# ProDoc_TwinWave_2026-01-11.net
KiCad netlist of a schematic drawn in EasyEDA Pro
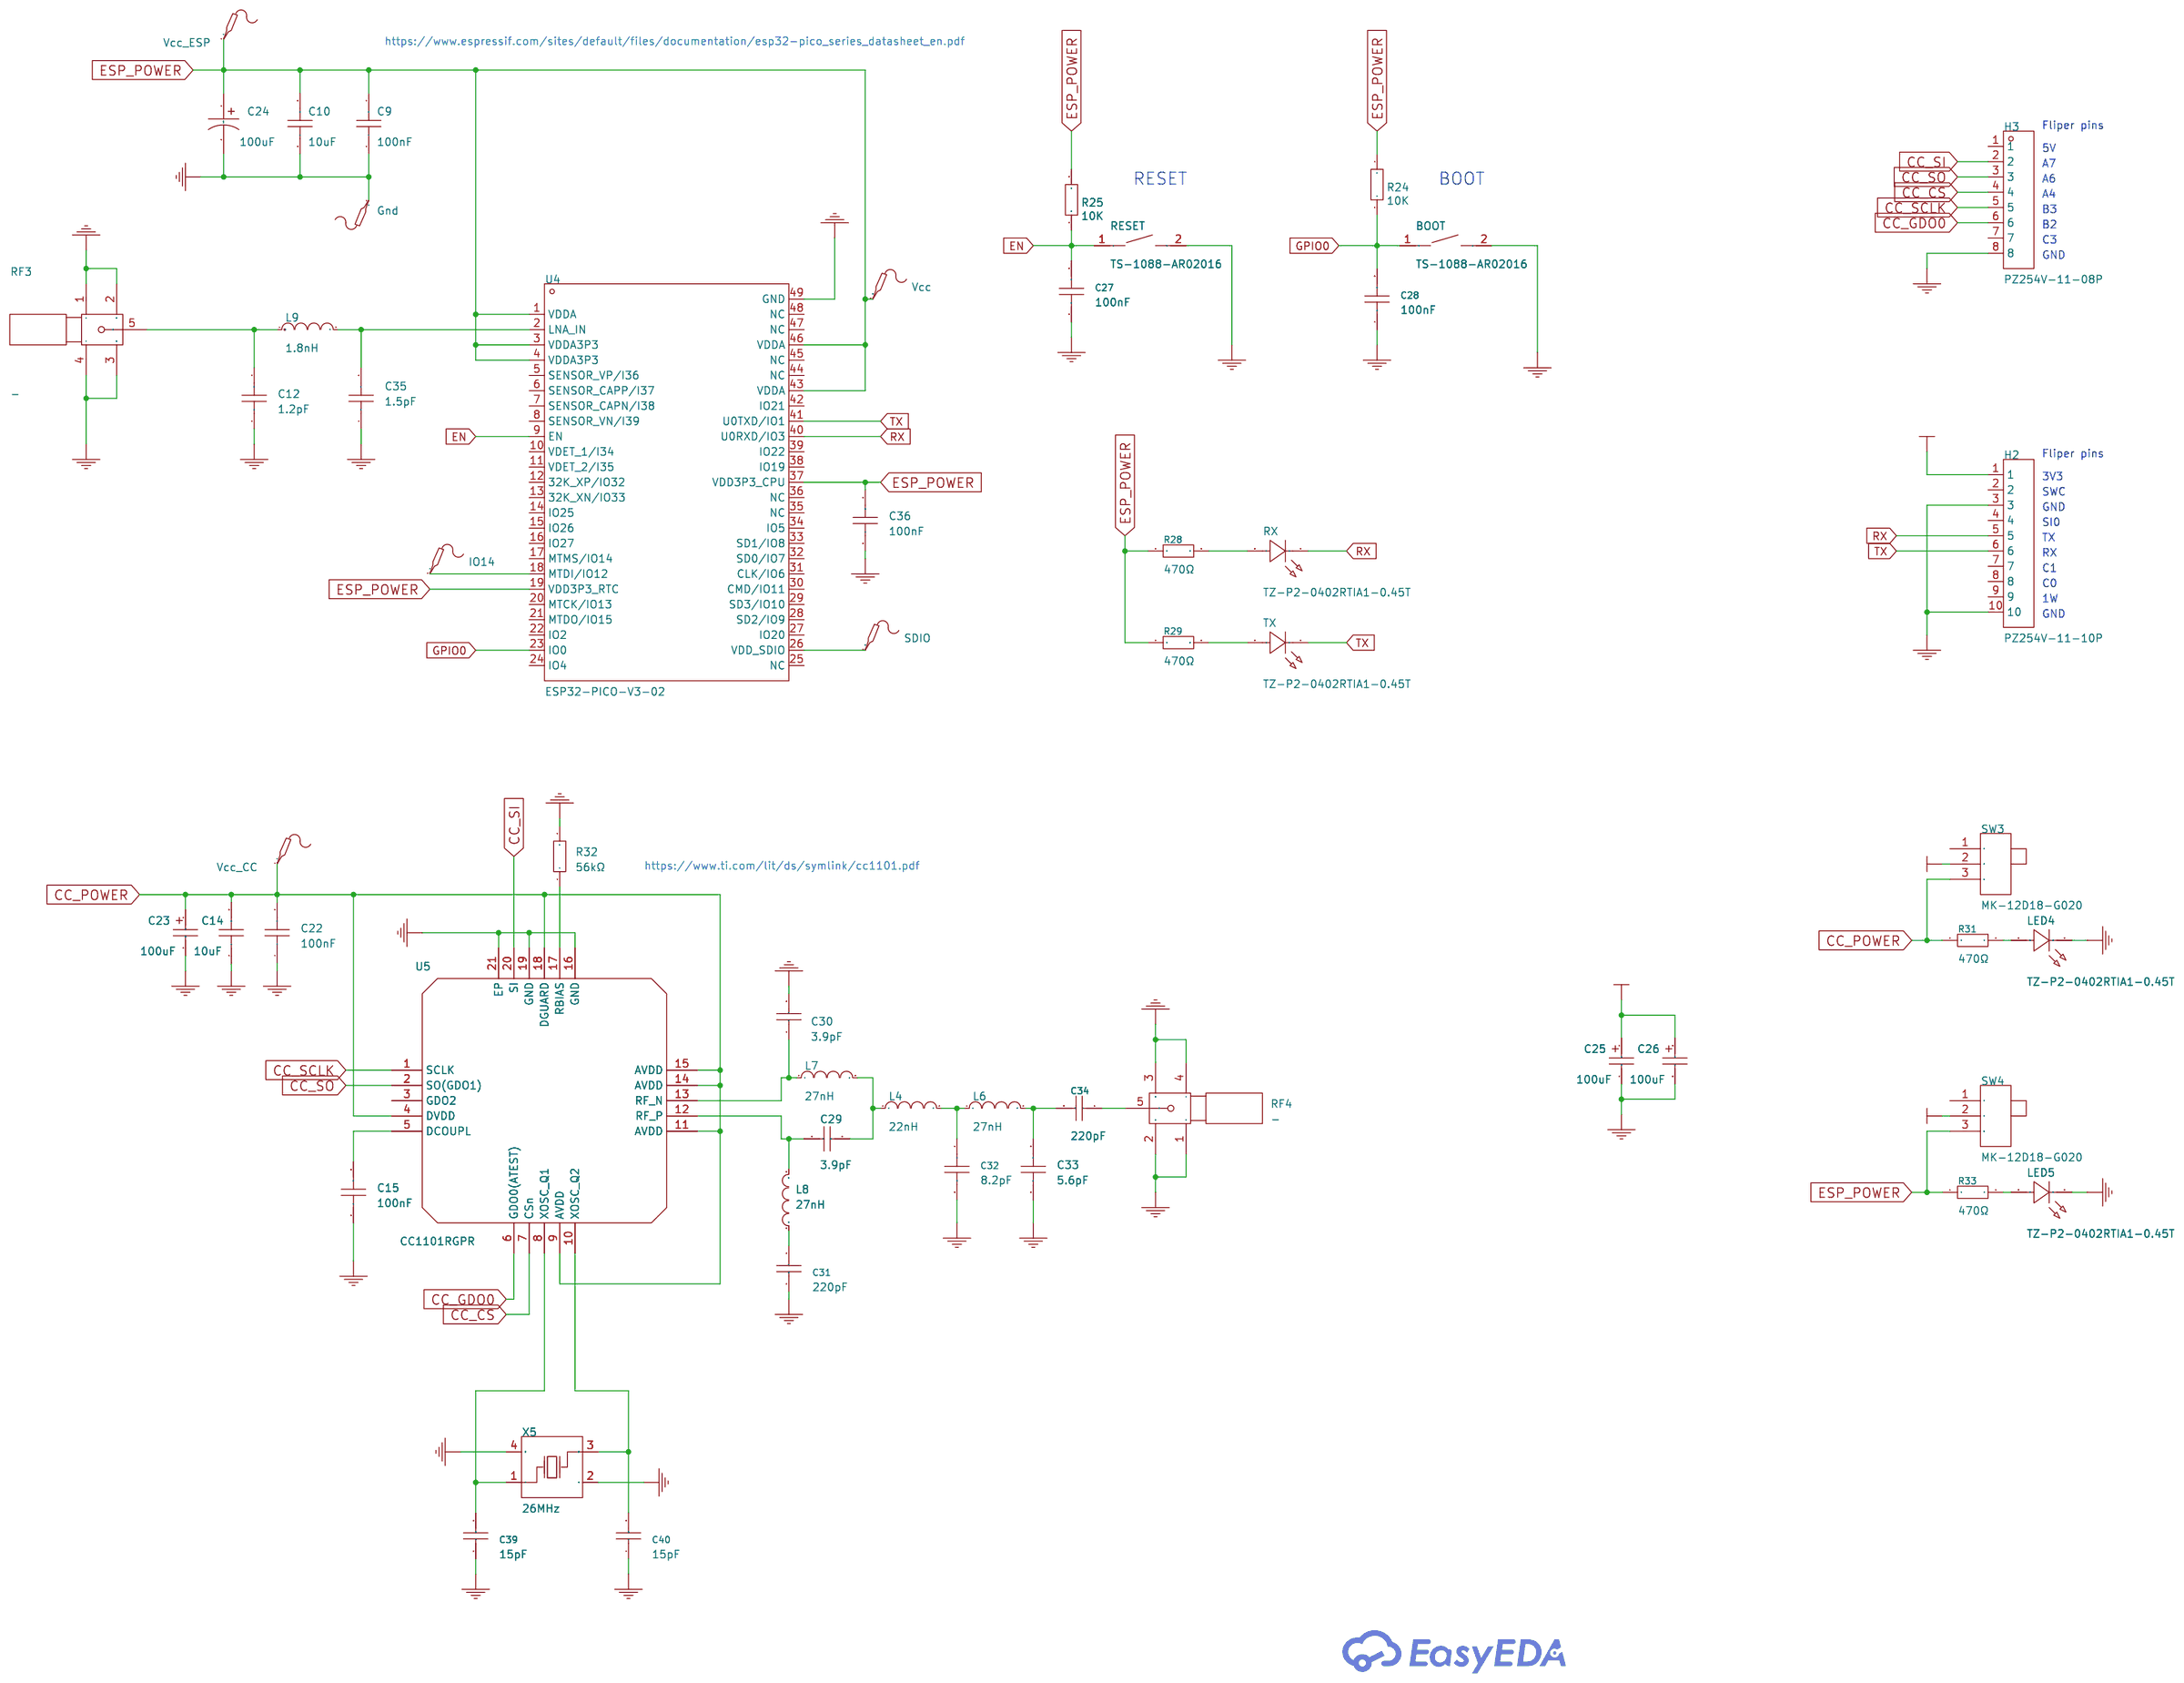
[diagram p0: schematic sheet]

(export (version "E")
  (design (tool "Eeschema 10.0.6"))
  (components
    (comp (ref "BOOT")
      (value "TS-1088-AR02016")
      (footprint "easyedapro:SW-SMD_L3.9-W3.0-P4.45")
      (fields (field (name "Manufacturer") "XUNPU(讯普)"))
      (libsource (lib "easyedapro") (part "TS-1088-AR02016"))
    )
    (comp (ref "C9")
      (value "100nF")
      (footprint "easyedapro:C0603")
      (description "Capacitance:100nF Tolerance:±10% Tolerance:±10% Voltage Rating:50V Temperature Coefficient:X7R")
      (fields
        (field (name "Manufacturer Part") "CC0603KRX7R9BB104")
        (field (name "Manufacturer") "YAGEO(国巨)")
      )
      (libsource (lib "easyedapro") (part "CC0603KRX7R9BB104"))
    )
    (comp (ref "C10")
      (value "10uF")
      (footprint "easyedapro:C0603")
      (fields
        (field (name "Manufacturer Part") "CL10A106MP8NNNC")
        (field (name "Manufacturer") "SAMSUNG(三星)")
      )
      (libsource (lib "easyedapro") (part "CL10A106MP8NNNC"))
    )
    (comp (ref "C12")
      (value "1.2pF")
      (footprint "easyedapro:C0201")
      (fields
        (field (name "Manufacturer Part") "GRM0335C1H1R2BA01D")
        (field (name "Manufacturer") "muRata(村田)")
      )
      (libsource (lib "easyedapro") (part "GRM0335C1H1R2BA01D"))
    )
    (comp (ref "C14")
      (value "10uF")
      (footprint "easyedapro:C0603")
      (fields
        (field (name "Manufacturer Part") "CL10A106MP8NNNC")
        (field (name "Manufacturer") "SAMSUNG(三星)")
      )
      (libsource (lib "easyedapro") (part "CL10A106MP8NNNC"))
    )
    (comp (ref "C15")
      (value "100nF")
      (footprint "easyedapro:C0603")
      (description "Capacitance:100nF Tolerance:±10% Tolerance:±10% Voltage Rating:50V Temperature Coefficient:X7R")
      (fields
        (field (name "Manufacturer Part") "CC0603KRX7R9BB104")
        (field (name "Manufacturer") "YAGEO(国巨)")
      )
      (libsource (lib "easyedapro") (part "CC0603KRX7R9BB104"))
    )
    (comp (ref "C22")
      (value "100nF")
      (footprint "easyedapro:C0603")
      (description "Capacitance:100nF Tolerance:±10% Tolerance:±10% Voltage Rating:50V Temperature Coefficient:X7R")
      (fields
        (field (name "Manufacturer Part") "CC0603KRX7R9BB104")
        (field (name "Manufacturer") "YAGEO(国巨)")
      )
      (libsource (lib "easyedapro") (part "CC0603KRX7R9BB104"))
    )
    (comp (ref "C23")
      (value "100uF")
      (footprint "easyedapro:CASE-B_3528")
      (fields (field (name "Manufacturer Part") "TAJB107K006RNJ") (field (name "Manufacturer") "Kyocera AVX"))
      (libsource (lib "easyedapro") (part "TAJB107K006RNJ"))
    )
    (comp (ref "C24")
      (value "100uF")
      (footprint "easyedapro:CASE-B_3528-1")
      (fields
        (field (name "Manufacturer Part") "TPSB107K006R0250")
        (field (name "Manufacturer") "Kyocera AVX")
      )
      (libsource (lib "easyedapro") (part "TPSB107K006R0250"))
    )
    (comp (ref "C25")
      (value "100uF")
      (footprint "easyedapro:CASE-B_3528")
      (fields (field (name "Manufacturer Part") "TAJB107K006RNJ") (field (name "Manufacturer") "Kyocera AVX"))
      (libsource (lib "easyedapro") (part "TAJB107K006RNJ"))
    )
    (comp (ref "C26")
      (value "100uF")
      (footprint "easyedapro:CASE-B_3528")
      (fields (field (name "Manufacturer Part") "TAJB107K006RNJ") (field (name "Manufacturer") "Kyocera AVX"))
      (libsource (lib "easyedapro") (part "TAJB107K006RNJ"))
    )
    (comp (ref "C27")
      (value "100nF")
      (footprint "easyedapro:C0402")
      (fields
        (field (name "Manufacturer Part") "CC0402KRX7R7BB104")
        (field (name "Manufacturer") "YAGEO(国巨)")
      )
      (libsource (lib "easyedapro") (part "CC0402KRX7R7BB104"))
    )
    (comp (ref "C28")
      (value "100nF")
      (footprint "easyedapro:C0402")
      (fields
        (field (name "Manufacturer Part") "CC0402KRX7R7BB104")
        (field (name "Manufacturer") "YAGEO(国巨)")
      )
      (libsource (lib "easyedapro") (part "CC0402KRX7R7BB104"))
    )
    (comp (ref "C29")
      (value "3.9pF")
      (footprint "easyedapro:C0402")
      (fields (field (name "Manufacturer Part") "0402CG3R9C500NT") (field (name "Manufacturer") "FH(风华)"))
      (libsource (lib "easyedapro") (part "0402CG3R9C500NT"))
    )
    (comp (ref "C30")
      (value "3.9pF")
      (footprint "easyedapro:C0402")
      (fields (field (name "Manufacturer Part") "0402CG3R9C500NT") (field (name "Manufacturer") "FH(风华)"))
      (libsource (lib "easyedapro") (part "0402CG3R9C500NT"))
    )
    (comp (ref "C31")
      (value "220pF")
      (footprint "easyedapro:C0402")
      (description "Capacitance:220pF Tolerance:±5% Tolerance:±5% Voltage Rating:50V Temperature Coefficient:NP0")
      (fields
        (field (name "Manufacturer Part") "CC0402JRNPO9BN221")
        (field (name "Manufacturer") "YAGEO(国巨)")
      )
      (libsource (lib "easyedapro") (part "CC0402JRNPO9BN221"))
    )
    (comp (ref "C32")
      (value "8.2pF")
      (footprint "easyedapro:C0402")
      (fields
        (field (name "Manufacturer Part") "CC0402BRNPO9BN8R2")
        (field (name "Manufacturer") "YAGEO(国巨)")
      )
      (libsource (lib "easyedapro") (part "CC0402BRNPO9BN8R2"))
    )
    (comp (ref "C33")
      (value "5.6pF")
      (footprint "easyedapro:C0402")
      (fields
        (field (name "Manufacturer Part") "CC0402BRNPO9BN5R6")
        (field (name "Manufacturer") "YAGEO(国巨)")
      )
      (libsource (lib "easyedapro") (part "CC0402BRNPO9BN5R6"))
    )
    (comp (ref "C34")
      (value "220pF")
      (footprint "easyedapro:C0402")
      (description "Capacitance:220pF Tolerance:±5% Tolerance:±5% Voltage Rating:50V Temperature Coefficient:NP0")
      (fields
        (field (name "Manufacturer Part") "CC0402JRNPO9BN221")
        (field (name "Manufacturer") "YAGEO(国巨)")
      )
      (libsource (lib "easyedapro") (part "CC0402JRNPO9BN221"))
    )
    (comp (ref "C35")
      (value "1.5pF")
      (footprint "easyedapro:C0201")
      (fields
        (field (name "Manufacturer Part") "GRM0335C1H1R5BA01D")
        (field (name "Manufacturer") "muRata(村田)")
      )
      (libsource (lib "easyedapro") (part "GRM0335C1H1R5BA01D"))
    )
    (comp (ref "C36")
      (value "100nF")
      (footprint "easyedapro:C0603")
      (description "Capacitance:100nF Tolerance:±10% Tolerance:±10% Voltage Rating:50V Temperature Coefficient:X7R")
      (fields
        (field (name "Manufacturer Part") "CC0603KRX7R9BB104")
        (field (name "Manufacturer") "YAGEO(国巨)")
      )
      (libsource (lib "easyedapro") (part "CC0603KRX7R9BB104"))
    )
    (comp (ref "C39")
      (value "15pF")
      (footprint "easyedapro:C0402")
      (fields
        (field (name "Manufacturer Part") "CC0402JRNPO9BN150")
        (field (name "Manufacturer") "YAGEO(国巨)")
      )
      (libsource (lib "easyedapro") (part "CC0402JRNPO9BN150"))
    )
    (comp (ref "C40")
      (value "15pF")
      (footprint "easyedapro:C0402")
      (fields
        (field (name "Manufacturer Part") "CC0402JRNPO9BN150")
        (field (name "Manufacturer") "YAGEO(国巨)")
      )
      (libsource (lib "easyedapro") (part "CC0402JRNPO9BN150"))
    )
    (comp (ref "Gnd")
      (value "~")
      (footprint "easyedapro:Test-Point-0.5mm")
      (description "Test Point 测试点")
      (libsource (lib "easyedapro") (part "Test-Point"))
    )
    (comp (ref "H2")
      (value "PZ254V-11-10P")
      (footprint "easyedapro:HDR-TH_10P-P2.54-V-M")
      (fields (field (name "Manufacturer") "XFCN(兴飞)"))
      (libsource (lib "easyedapro") (part "PZ254V-11-10P"))
    )
    (comp (ref "H3")
      (value "PZ254V-11-08P")
      (footprint "easyedapro:HDR-TH_8P-P2.54-V-M")
      (fields (field (name "Manufacturer") "XFCN(兴飞)"))
      (libsource (lib "easyedapro") (part "PZ254V-11-08P"))
    )
    (comp (ref "IO14")
      (value "~")
      (footprint "easyedapro:Test-Point-0.5mm")
      (description "Test Point 测试点")
      (libsource (lib "easyedapro") (part "Test-Point"))
    )
    (comp (ref "L4")
      (value "22nH")
      (footprint "easyedapro:L0402")
      (fields (field (name "Manufacturer Part") "LQG15HS22NJ02D") (field (name "Manufacturer") "muRata(村田)"))
      (libsource (lib "easyedapro") (part "LQG15HS22NJ02D"))
    )
    (comp (ref "L6")
      (value "27nH")
      (footprint "easyedapro:L0402-RD")
      (fields (field (name "Manufacturer Part") "LQG15HS27NJ02D") (field (name "Manufacturer") "muRata(村田)"))
      (libsource (lib "easyedapro") (part "LQG15HS27NJ02D"))
    )
    (comp (ref "L7")
      (value "27nH")
      (footprint "easyedapro:L0402-RD")
      (fields (field (name "Manufacturer Part") "LQG15HS27NJ02D") (field (name "Manufacturer") "muRata(村田)"))
      (libsource (lib "easyedapro") (part "LQG15HS27NJ02D"))
    )
    (comp (ref "L8")
      (value "27nH")
      (footprint "easyedapro:L0402-RD")
      (fields (field (name "Manufacturer Part") "LQG15HS27NJ02D") (field (name "Manufacturer") "muRata(村田)"))
      (libsource (lib "easyedapro") (part "LQG15HS27NJ02D"))
    )
    (comp (ref "L9")
      (value "1.8nH")
      (footprint "easyedapro:L0201-RD")
      (fields (field (name "Manufacturer Part") "LQP03TN1N8B02D") (field (name "Manufacturer") "muRata(村田)"))
      (libsource (lib "easyedapro") (part "LQP03TN1N8B02D"))
    )
    (comp (ref "LED4")
      (value "TZ-P2-0402RTIA1-0.45T")
      (footprint "easyedapro:LED0402-RD_RED")
      (fields (field (name "Manufacturer") "TUOZHAN(拓展光电)"))
      (libsource (lib "easyedapro") (part "TZ-P2-0402RTIA1-0.45T"))
    )
    (comp (ref "LED5")
      (value "TZ-P2-0402RTIA1-0.45T")
      (footprint "easyedapro:LED0402-RD_RED")
      (fields (field (name "Manufacturer") "TUOZHAN(拓展光电)"))
      (libsource (lib "easyedapro") (part "TZ-P2-0402RTIA1-0.45T"))
    )
    (comp (ref "R24")
      (value "10K")
      (footprint "easyedapro:R0603")
      (fields (field (name "Manufacturer Part") "RC0603DR-0710KL") (field (name "Manufacturer") "YAGEO(国巨)"))
      (libsource (lib "easyedapro") (part "10K"))
    )
    (comp (ref "R25")
      (value "10K")
      (footprint "easyedapro:R0603")
      (fields (field (name "Manufacturer Part") "RC0603DR-0710KL") (field (name "Manufacturer") "YAGEO(国巨)"))
      (libsource (lib "easyedapro") (part "10K"))
    )
    (comp (ref "R28")
      (value "470Ω")
      (footprint "easyedapro:R0402")
      (fields
        (field (name "Manufacturer Part") "0402WGF4700TCE")
        (field (name "Manufacturer") "UNI-ROYAL(厚声)")
      )
      (libsource (lib "easyedapro") (part "0402WGF4700TCE"))
    )
    (comp (ref "R29")
      (value "470Ω")
      (footprint "easyedapro:R0402")
      (fields
        (field (name "Manufacturer Part") "0402WGF4700TCE")
        (field (name "Manufacturer") "UNI-ROYAL(厚声)")
      )
      (libsource (lib "easyedapro") (part "0402WGF4700TCE"))
    )
    (comp (ref "R31")
      (value "470Ω")
      (footprint "easyedapro:R0402")
      (fields
        (field (name "Manufacturer Part") "0402WGF4700TCE")
        (field (name "Manufacturer") "UNI-ROYAL(厚声)")
      )
      (libsource (lib "easyedapro") (part "0402WGF4700TCE"))
    )
    (comp (ref "R32")
      (value "56kΩ")
      (footprint "easyedapro:R0402")
      (fields
        (field (name "Manufacturer Part") "0402WGF5602TCE")
        (field (name "Manufacturer") "UNI-ROYAL(厚声)")
      )
      (libsource (lib "easyedapro") (part "0402WGF5602TCE"))
    )
    (comp (ref "R33")
      (value "470Ω")
      (footprint "easyedapro:R0402")
      (fields
        (field (name "Manufacturer Part") "0402WGF4700TCE")
        (field (name "Manufacturer") "UNI-ROYAL(厚声)")
      )
      (libsource (lib "easyedapro") (part "0402WGF4700TCE"))
    )
    (comp (ref "RESET")
      (value "TS-1088-AR02016")
      (footprint "easyedapro:SW-SMD_L3.9-W3.0-P4.45")
      (fields (field (name "Manufacturer") "XUNPU(讯普)"))
      (libsource (lib "easyedapro") (part "TS-1088-AR02016"))
    )
    (comp (ref "RF3")
      (value "-")
      (footprint "easyedapro:SMA-SMD_BWSMA-KE-P001")
      (fields
        (field (name "Manufacturer Part") "BWSMA-KE-P001")
        (field (name "Manufacturer") "BAT WIRELESS(蝙蝠无线)")
      )
      (libsource (lib "easyedapro") (part "BWSMA-KE-P001"))
    )
    (comp (ref "RF4")
      (value "-")
      (footprint "easyedapro:SMA-SMD_BWSMA-KE-P001")
      (fields
        (field (name "Manufacturer Part") "BWSMA-KE-P001")
        (field (name "Manufacturer") "BAT WIRELESS(蝙蝠无线)")
      )
      (libsource (lib "easyedapro") (part "BWSMA-KE-P001"))
    )
    (comp (ref "RX")
      (value "TZ-P2-0402RTIA1-0.45T")
      (footprint "easyedapro:LED0402-RD_RED")
      (fields (field (name "Manufacturer") "TUOZHAN(拓展光电)"))
      (libsource (lib "easyedapro") (part "TZ-P2-0402RTIA1-0.45T"))
    )
    (comp (ref "SDIO")
      (value "~")
      (footprint "easyedapro:Test-Point-0.5mm")
      (description "Test Point 测试点")
      (libsource (lib "easyedapro") (part "Test-Point"))
    )
    (comp (ref "SW3")
      (value "MK-12D18-G020")
      (footprint "easyedapro:SW-TH_MK-12D18-G040")
      (fields (field (name "Manufacturer") "G-Switch(品赞)"))
      (libsource (lib "easyedapro") (part "MK-12D18-G020"))
    )
    (comp (ref "SW4")
      (value "MK-12D18-G020")
      (footprint "easyedapro:SW-TH_MK-12D18-G040")
      (fields (field (name "Manufacturer") "G-Switch(品赞)"))
      (libsource (lib "easyedapro") (part "MK-12D18-G020"))
    )
    (comp (ref "TX")
      (value "TZ-P2-0402RTIA1-0.45T")
      (footprint "easyedapro:LED0402-RD_RED")
      (fields (field (name "Manufacturer") "TUOZHAN(拓展光电)"))
      (libsource (lib "easyedapro") (part "TZ-P2-0402RTIA1-0.45T"))
    )
    (comp (ref "U4")
      (value "ESP32-PICO-V3-02")
      (footprint "easyedapro:QFN-48_L7.0-W7.0-P0.50-BL-EP5.1")
      (fields (field (name "Manufacturer") "ESPRESSIF(乐鑫)"))
      (libsource (lib "easyedapro") (part "ESP32-PICO-V3-02"))
    )
    (comp (ref "U5")
      (value "CC1101RGPR")
      (footprint "easyedapro:QFN-20_L4.0-W4.0-P0.5-TL-EP")
      (fields (field (name "Manufacturer") "TI(德州仪器)"))
      (libsource (lib "easyedapro") (part "CC1101RGPR"))
    )
    (comp (ref "Vcc")
      (value "~")
      (footprint "easyedapro:Test-Point-0.5mm")
      (description "Test Point 测试点")
      (libsource (lib "easyedapro") (part "Test-Point"))
    )
    (comp (ref "Vcc_CC")
      (value "~")
      (footprint "easyedapro:Test-Point-0.5mm")
      (description "Test Point 测试点")
      (libsource (lib "easyedapro") (part "Test-Point"))
    )
    (comp (ref "Vcc_ESP")
      (value "~")
      (footprint "easyedapro:Test-Point-0.5mm")
      (description "Test Point 测试点")
      (libsource (lib "easyedapro") (part "Test-Point"))
    )
    (comp (ref "X5")
      (value "26MHz")
      (footprint "easyedapro:CRYSTAL-SMD_4P-L3.2-W2.5-BL")
      (fields (field (name "Manufacturer Part") "X322526MMB4SI") (field (name "Manufacturer") "YXC(扬兴晶振)"))
      (libsource (lib "easyedapro") (part "X322526MMB4SI"))
    )
  )
  (nets
    (net (code "1") (name "3V3") (class "Default")
      (node (ref "C25") (pin "1") (pinfunction "1_1") (pintype "input"))
      (node (ref "C26") (pin "1") (pinfunction "1_1") (pintype "input"))
      (node (ref "H2") (pin "1") (pinfunction "1_1") (pintype "unspecified"))
      (node (ref "SW3") (pin "2") (pinfunction "2_2") (pintype "unspecified"))
      (node (ref "SW4") (pin "2") (pinfunction "2_2") (pintype "unspecified"))
    )
    (net (code "2") (name "CC_CS") (class "Default")
      (node (ref "H3") (pin "4") (pinfunction "4_4") (pintype "unspecified"))
      (node (ref "U5") (pin "7") (pinfunction "CSn_7") (pintype "unspecified"))
    )
    (net (code "3") (name "CC_GDO0") (class "Default")
      (node (ref "H3") (pin "6") (pinfunction "6_6") (pintype "unspecified"))
      (node (ref "U5") (pin "6") (pinfunction "GDO0(ATEST)_6") (pintype "unspecified"))
    )
    (net (code "4") (name "CC_POWER") (class "Default")
      (node (ref "C14") (pin "2") (pinfunction "2_2") (pintype "unspecified"))
      (node (ref "C22") (pin "2") (pinfunction "2_2") (pintype "unspecified"))
      (node (ref "C23") (pin "1") (pinfunction "1_1") (pintype "input"))
      (node (ref "R31") (pin "1") (pinfunction "1_1") (pintype "input"))
      (node (ref "SW3") (pin "3") (pinfunction "3_3") (pintype "unspecified"))
      (node (ref "U5") (pin "11") (pinfunction "AVDD_11") (pintype "unspecified"))
      (node (ref "U5") (pin "14") (pinfunction "AVDD_14") (pintype "unspecified"))
      (node (ref "U5") (pin "15") (pinfunction "AVDD_15") (pintype "unspecified"))
      (node (ref "U5") (pin "18") (pinfunction "DGUARD_18") (pintype "unspecified"))
      (node (ref "U5") (pin "4") (pinfunction "DVDD_4") (pintype "unspecified"))
      (node (ref "U5") (pin "9") (pinfunction "AVDD_9") (pintype "unspecified"))
      (node (ref "Vcc_CC") (pin "1") (pinfunction "1_1") (pintype "unspecified"))
    )
    (net (code "5") (name "CC_SCLK") (class "Default")
      (node (ref "H3") (pin "5") (pinfunction "5_5") (pintype "unspecified"))
      (node (ref "U5") (pin "1") (pinfunction "SCLK_1") (pintype "unspecified"))
    )
    (net (code "6") (name "CC_SI") (class "Default")
      (node (ref "H3") (pin "2") (pinfunction "2_2") (pintype "unspecified"))
      (node (ref "U5") (pin "20") (pinfunction "SI_20") (pintype "unspecified"))
    )
    (net (code "7") (name "CC_SO") (class "Default")
      (node (ref "H3") (pin "3") (pinfunction "3_3") (pintype "unspecified"))
      (node (ref "U5") (pin "2") (pinfunction "SO(GDO1)_2") (pintype "unspecified"))
    )
    (net (code "8") (name "EN") (class "Default")
      (node (ref "C27") (pin "2") (pinfunction "2_2") (pintype "input"))
      (node (ref "R25") (pin "1") (pinfunction "1_1") (pintype "input"))
      (node (ref "RESET") (pin "1") (pinfunction "1_1") (pintype "unspecified"))
      (node (ref "U4") (pin "9") (pinfunction "EN_9") (pintype "unspecified"))
    )
    (net (code "9") (name "ESP_POWER") (class "Default")
      (node (ref "C10") (pin "2") (pinfunction "2_2") (pintype "unspecified"))
      (node (ref "C24") (pin "1") (pinfunction "1_1") (pintype "unspecified"))
      (node (ref "C36") (pin "2") (pinfunction "2_2") (pintype "unspecified"))
      (node (ref "C9") (pin "2") (pinfunction "2_2") (pintype "unspecified"))
      (node (ref "R24") (pin "2") (pinfunction "2_2") (pintype "input"))
      (node (ref "R25") (pin "2") (pinfunction "2_2") (pintype "input"))
      (node (ref "R28") (pin "1") (pinfunction "1_1") (pintype "input"))
      (node (ref "R29") (pin "1") (pinfunction "1_1") (pintype "input"))
      (node (ref "R33") (pin "1") (pinfunction "1_1") (pintype "input"))
      (node (ref "SW4") (pin "3") (pinfunction "3_3") (pintype "unspecified"))
      (node (ref "U4") (pin "1") (pinfunction "VDDA_1") (pintype "unspecified"))
      (node (ref "U4") (pin "19") (pinfunction "VDD3P3_RTC_19") (pintype "unspecified"))
      (node (ref "U4") (pin "3") (pinfunction "VDDA3P3_3") (pintype "unspecified"))
      (node (ref "U4") (pin "37") (pinfunction "VDD3P3_CPU_37") (pintype "unspecified"))
      (node (ref "U4") (pin "4") (pinfunction "VDDA3P3_4") (pintype "unspecified"))
      (node (ref "U4") (pin "43") (pinfunction "VDDA_43") (pintype "unspecified"))
      (node (ref "U4") (pin "46") (pinfunction "VDDA_46") (pintype "unspecified"))
      (node (ref "Vcc") (pin "1") (pinfunction "1_1") (pintype "unspecified"))
      (node (ref "Vcc_ESP") (pin "1") (pinfunction "1_1") (pintype "unspecified"))
    )
    (net (code "10") (name "GND") (class "Default")
      (node (ref "BOOT") (pin "2") (pinfunction "2_2") (pintype "unspecified"))
      (node (ref "C10") (pin "1") (pinfunction "1_1") (pintype "unspecified"))
      (node (ref "C12") (pin "1") (pinfunction "1_1") (pintype "unspecified"))
      (node (ref "C14") (pin "1") (pinfunction "1_1") (pintype "unspecified"))
      (node (ref "C15") (pin "1") (pinfunction "1_1") (pintype "unspecified"))
      (node (ref "C22") (pin "1") (pinfunction "1_1") (pintype "unspecified"))
      (node (ref "C23") (pin "2") (pinfunction "2_2") (pintype "input"))
      (node (ref "C24") (pin "2") (pinfunction "2_2") (pintype "unspecified"))
      (node (ref "C25") (pin "2") (pinfunction "2_2") (pintype "input"))
      (node (ref "C26") (pin "2") (pinfunction "2_2") (pintype "input"))
      (node (ref "C27") (pin "1") (pinfunction "1_1") (pintype "input"))
      (node (ref "C28") (pin "1") (pinfunction "1_1") (pintype "input"))
      (node (ref "C30") (pin "2") (pinfunction "2_2") (pintype "input"))
      (node (ref "C31") (pin "1") (pinfunction "1_1") (pintype "input"))
      (node (ref "C32") (pin "2") (pinfunction "2_2") (pintype "input"))
      (node (ref "C33") (pin "1") (pinfunction "1_1") (pintype "unspecified"))
      (node (ref "C35") (pin "1") (pinfunction "1_1") (pintype "unspecified"))
      (node (ref "C36") (pin "1") (pinfunction "1_1") (pintype "unspecified"))
      (node (ref "C39") (pin "1") (pinfunction "1_1") (pintype "input"))
      (node (ref "C40") (pin "1") (pinfunction "1_1") (pintype "input"))
      (node (ref "C9") (pin "1") (pinfunction "1_1") (pintype "unspecified"))
      (node (ref "Gnd") (pin "1") (pinfunction "1_1") (pintype "unspecified"))
      (node (ref "H2") (pin "10") (pinfunction "10_10") (pintype "unspecified"))
      (node (ref "H2") (pin "3") (pinfunction "3_3") (pintype "unspecified"))
      (node (ref "H3") (pin "8") (pinfunction "8_8") (pintype "unspecified"))
      (node (ref "LED4") (pin "1") (pinfunction "K_1") (pintype "unspecified"))
      (node (ref "LED5") (pin "1") (pinfunction "K_1") (pintype "unspecified"))
      (node (ref "R32") (pin "2") (pinfunction "2_2") (pintype "input"))
      (node (ref "RESET") (pin "2") (pinfunction "2_2") (pintype "unspecified"))
      (node (ref "RF3") (pin "1") (pinfunction "1_1") (pintype "unspecified"))
      (node (ref "RF3") (pin "2") (pinfunction "2_2") (pintype "unspecified"))
      (node (ref "RF3") (pin "3") (pinfunction "3_3") (pintype "unspecified"))
      (node (ref "RF3") (pin "4") (pinfunction "4_4") (pintype "unspecified"))
      (node (ref "RF4") (pin "1") (pinfunction "1_1") (pintype "unspecified"))
      (node (ref "RF4") (pin "2") (pinfunction "2_2") (pintype "unspecified"))
      (node (ref "RF4") (pin "3") (pinfunction "3_3") (pintype "unspecified"))
      (node (ref "RF4") (pin "4") (pinfunction "4_4") (pintype "unspecified"))
      (node (ref "U4") (pin "49") (pinfunction "GND_49") (pintype "unspecified"))
      (node (ref "U5") (pin "16") (pinfunction "GND_16") (pintype "unspecified"))
      (node (ref "U5") (pin "19") (pinfunction "GND_19") (pintype "unspecified"))
      (node (ref "U5") (pin "21") (pinfunction "EP_21") (pintype "unspecified"))
      (node (ref "X5") (pin "2") (pinfunction "GND_2") (pintype "unspecified"))
      (node (ref "X5") (pin "4") (pinfunction "GND_4") (pintype "unspecified"))
    )
    (net (code "11") (name "GPIO0") (class "Default")
      (node (ref "BOOT") (pin "1") (pinfunction "1_1") (pintype "unspecified"))
      (node (ref "C28") (pin "2") (pinfunction "2_2") (pintype "input"))
      (node (ref "R24") (pin "1") (pinfunction "1_1") (pintype "input"))
      (node (ref "U4") (pin "23") (pinfunction "IO0_23") (pintype "unspecified"))
    )
    (net (code "12") (name "Net-(C12-Pad2)") (class "Default")
      (node (ref "C12") (pin "2") (pinfunction "2_2") (pintype "unspecified"))
      (node (ref "L9") (pin "1") (pinfunction "1_1") (pintype "input"))
      (node (ref "RF3") (pin "5") (pinfunction "5_5") (pintype "unspecified"))
    )
    (net (code "13") (name "Net-(C29-Pad2)") (class "Default")
      (node (ref "C29") (pin "2") (pinfunction "2_2") (pintype "input"))
      (node (ref "L4") (pin "1") (pinfunction "1_1") (pintype "unspecified"))
      (node (ref "L7") (pin "2") (pinfunction "2_2") (pintype "unspecified"))
    )
    (net (code "14") (name "Net-(C31-Pad2)") (class "Default")
      (node (ref "C31") (pin "2") (pinfunction "2_2") (pintype "input"))
      (node (ref "L8") (pin "1") (pinfunction "1_1") (pintype "unspecified"))
    )
    (net (code "15") (name "Net-(C32-Pad1)") (class "Default")
      (node (ref "C32") (pin "1") (pinfunction "1_1") (pintype "input"))
      (node (ref "L4") (pin "2") (pinfunction "2_2") (pintype "unspecified"))
      (node (ref "L6") (pin "1") (pinfunction "1_1") (pintype "unspecified"))
    )
    (net (code "16") (name "Net-(C33-Pad2)") (class "Default")
      (node (ref "C33") (pin "2") (pinfunction "2_2") (pintype "unspecified"))
      (node (ref "C34") (pin "2") (pinfunction "2_2") (pintype "input"))
      (node (ref "L6") (pin "2") (pinfunction "2_2") (pintype "unspecified"))
    )
    (net (code "17") (name "Net-(C34-Pad1)") (class "Default")
      (node (ref "C34") (pin "1") (pinfunction "1_1") (pintype "input"))
      (node (ref "RF4") (pin "5") (pinfunction "5_5") (pintype "unspecified"))
    )
    (net (code "18") (name "Net-(LED4-A)") (class "Default")
      (node (ref "LED4") (pin "2") (pinfunction "A_2") (pintype "unspecified"))
      (node (ref "R31") (pin "2") (pinfunction "2_2") (pintype "input"))
    )
    (net (code "19") (name "Net-(LED5-A)") (class "Default")
      (node (ref "LED5") (pin "2") (pinfunction "A_2") (pintype "unspecified"))
      (node (ref "R33") (pin "2") (pinfunction "2_2") (pintype "input"))
    )
    (net (code "20") (name "Net-(RX-A)") (class "Default")
      (node (ref "R28") (pin "2") (pinfunction "2_2") (pintype "input"))
      (node (ref "RX") (pin "2") (pinfunction "A_2") (pintype "unspecified"))
    )
    (net (code "21") (name "Net-(TX-A)") (class "Default")
      (node (ref "R29") (pin "2") (pinfunction "2_2") (pintype "input"))
      (node (ref "TX") (pin "2") (pinfunction "A_2") (pintype "unspecified"))
    )
    (net (code "22") (name "Net-(U4-LNA_IN)") (class "Default")
      (node (ref "C35") (pin "2") (pinfunction "2_2") (pintype "unspecified"))
      (node (ref "L9") (pin "2") (pinfunction "2_2") (pintype "input"))
      (node (ref "U4") (pin "2") (pinfunction "LNA_IN_2") (pintype "unspecified"))
    )
    (net (code "23") (name "Net-(U4-MTDI{slash}IO12)") (class "Default")
      (node (ref "IO14") (pin "1") (pinfunction "1_1") (pintype "unspecified"))
      (node (ref "U4") (pin "18") (pinfunction "MTDI/IO12_18") (pintype "unspecified"))
    )
    (net (code "24") (name "Net-(U4-VDD_SDIO)") (class "Default")
      (node (ref "SDIO") (pin "1") (pinfunction "1_1") (pintype "unspecified"))
      (node (ref "U4") (pin "26") (pinfunction "VDD_SDIO_26") (pintype "unspecified"))
    )
    (net (code "25") (name "Net-(U5-DCOUPL)") (class "Default")
      (node (ref "C15") (pin "2") (pinfunction "2_2") (pintype "unspecified"))
      (node (ref "U5") (pin "5") (pinfunction "DCOUPL_5") (pintype "unspecified"))
    )
    (net (code "26") (name "Net-(U5-RBIAS)") (class "Default")
      (node (ref "R32") (pin "1") (pinfunction "1_1") (pintype "input"))
      (node (ref "U5") (pin "17") (pinfunction "RBIAS_17") (pintype "unspecified"))
    )
    (net (code "27") (name "Net-(U5-RF_N)") (class "Default")
      (node (ref "C30") (pin "1") (pinfunction "1_1") (pintype "input"))
      (node (ref "L7") (pin "1") (pinfunction "1_1") (pintype "unspecified"))
      (node (ref "U5") (pin "13") (pinfunction "RF_N_13") (pintype "unspecified"))
    )
    (net (code "28") (name "Net-(U5-RF_P)") (class "Default")
      (node (ref "C29") (pin "1") (pinfunction "1_1") (pintype "input"))
      (node (ref "L8") (pin "2") (pinfunction "2_2") (pintype "unspecified"))
      (node (ref "U5") (pin "12") (pinfunction "RF_P_12") (pintype "unspecified"))
    )
    (net (code "29") (name "Net-(U5-XOSC_Q1)") (class "Default")
      (node (ref "C39") (pin "2") (pinfunction "2_2") (pintype "input"))
      (node (ref "U5") (pin "8") (pinfunction "XOSC_Q1_8") (pintype "unspecified"))
      (node (ref "X5") (pin "1") (pinfunction "OSC1_1") (pintype "unspecified"))
    )
    (net (code "30") (name "Net-(U5-XOSC_Q2)") (class "Default")
      (node (ref "C40") (pin "2") (pinfunction "2_2") (pintype "input"))
      (node (ref "U5") (pin "10") (pinfunction "XOSC_Q2_10") (pintype "unspecified"))
      (node (ref "X5") (pin "3") (pinfunction "OSC2_3") (pintype "unspecified"))
    )
    (net (code "31") (name "RX") (class "Default")
      (node (ref "H2") (pin "5") (pinfunction "5_5") (pintype "unspecified"))
      (node (ref "RX") (pin "1") (pinfunction "K_1") (pintype "unspecified"))
      (node (ref "U4") (pin "40") (pinfunction "U0RXD/IO3_40") (pintype "unspecified"))
    )
    (net (code "32") (name "TX") (class "Default")
      (node (ref "H2") (pin "6") (pinfunction "6_6") (pintype "unspecified"))
      (node (ref "TX") (pin "1") (pinfunction "K_1") (pintype "unspecified"))
      (node (ref "U4") (pin "41") (pinfunction "U0TXD/IO1_41") (pintype "unspecified"))
    )
    (net (code "33") (name "unconnected-(H2-Pad2)") (class "Default")
      (node (ref "H2") (pin "2") (pinfunction "2_2") (pintype "unspecified"))
    )
    (net (code "34") (name "unconnected-(H2-Pad4)") (class "Default")
      (node (ref "H2") (pin "4") (pinfunction "4_4") (pintype "unspecified"))
    )
    (net (code "35") (name "unconnected-(H2-Pad7)") (class "Default")
      (node (ref "H2") (pin "7") (pinfunction "7_7") (pintype "unspecified"))
    )
    (net (code "36") (name "unconnected-(H2-Pad8)") (class "Default")
      (node (ref "H2") (pin "8") (pinfunction "8_8") (pintype "unspecified"))
    )
    (net (code "37") (name "unconnected-(H2-Pad9)") (class "Default")
      (node (ref "H2") (pin "9") (pinfunction "9_9") (pintype "unspecified"))
    )
    (net (code "38") (name "unconnected-(H3-Pad1)") (class "Default")
      (node (ref "H3") (pin "1") (pinfunction "1_1") (pintype "unspecified"))
    )
    (net (code "39") (name "unconnected-(H3-Pad7)") (class "Default")
      (node (ref "H3") (pin "7") (pinfunction "7_7") (pintype "unspecified"))
    )
    (net (code "40") (name "unconnected-(SW3-Pad1)") (class "Default")
      (node (ref "SW3") (pin "1") (pinfunction "1_1") (pintype "unspecified"))
    )
    (net (code "41") (name "unconnected-(SW4-Pad1)") (class "Default")
      (node (ref "SW4") (pin "1") (pinfunction "1_1") (pintype "unspecified"))
    )
    (net (code "42") (name "unconnected-(U4-32K_XN{slash}IO33-Pad13)") (class "Default")
      (node (ref "U4") (pin "13") (pinfunction "32K_XN/IO33_13") (pintype "unspecified"))
    )
    (net (code "43") (name "unconnected-(U4-32K_XP{slash}IO32-Pad12)") (class "Default")
      (node (ref "U4") (pin "12") (pinfunction "32K_XP/IO32_12") (pintype "unspecified"))
    )
    (net (code "44") (name "unconnected-(U4-CLK{slash}IO6-Pad31)") (class "Default")
      (node (ref "U4") (pin "31") (pinfunction "CLK/IO6_31") (pintype "unspecified"))
    )
    (net (code "45") (name "unconnected-(U4-CMD{slash}IO11-Pad30)") (class "Default")
      (node (ref "U4") (pin "30") (pinfunction "CMD/IO11_30") (pintype "unspecified"))
    )
    (net (code "46") (name "unconnected-(U4-IO2-Pad22)") (class "Default")
      (node (ref "U4") (pin "22") (pinfunction "IO2_22") (pintype "unspecified"))
    )
    (net (code "47") (name "unconnected-(U4-IO4-Pad24)") (class "Default")
      (node (ref "U4") (pin "24") (pinfunction "IO4_24") (pintype "unspecified"))
    )
    (net (code "48") (name "unconnected-(U4-IO5-Pad34)") (class "Default")
      (node (ref "U4") (pin "34") (pinfunction "IO5_34") (pintype "unspecified"))
    )
    (net (code "49") (name "unconnected-(U4-IO19-Pad38)") (class "Default")
      (node (ref "U4") (pin "38") (pinfunction "IO19_38") (pintype "unspecified"))
    )
    (net (code "50") (name "unconnected-(U4-IO20-Pad27)") (class "Default")
      (node (ref "U4") (pin "27") (pinfunction "IO20_27") (pintype "unspecified"))
    )
    (net (code "51") (name "unconnected-(U4-IO21-Pad42)") (class "Default")
      (node (ref "U4") (pin "42") (pinfunction "IO21_42") (pintype "unspecified"))
    )
    (net (code "52") (name "unconnected-(U4-IO22-Pad39)") (class "Default")
      (node (ref "U4") (pin "39") (pinfunction "IO22_39") (pintype "unspecified"))
    )
    (net (code "53") (name "unconnected-(U4-IO25-Pad14)") (class "Default")
      (node (ref "U4") (pin "14") (pinfunction "IO25_14") (pintype "unspecified"))
    )
    (net (code "54") (name "unconnected-(U4-IO26-Pad15)") (class "Default")
      (node (ref "U4") (pin "15") (pinfunction "IO26_15") (pintype "unspecified"))
    )
    (net (code "55") (name "unconnected-(U4-IO27-Pad16)") (class "Default")
      (node (ref "U4") (pin "16") (pinfunction "IO27_16") (pintype "unspecified"))
    )
    (net (code "56") (name "unconnected-(U4-MTCK{slash}IO13-Pad20)") (class "Default")
      (node (ref "U4") (pin "20") (pinfunction "MTCK/IO13_20") (pintype "unspecified"))
    )
    (net (code "57") (name "unconnected-(U4-MTDO{slash}IO15-Pad21)") (class "Default")
      (node (ref "U4") (pin "21") (pinfunction "MTDO/IO15_21") (pintype "unspecified"))
    )
    (net (code "58") (name "unconnected-(U4-MTMS{slash}IO14-Pad17)") (class "Default")
      (node (ref "U4") (pin "17") (pinfunction "MTMS/IO14_17") (pintype "unspecified"))
    )
    (net (code "59") (name "unconnected-(U4-NC-Pad25)") (class "Default")
      (node (ref "U4") (pin "25") (pinfunction "NC_25") (pintype "unspecified"))
    )
    (net (code "60") (name "unconnected-(U4-NC-Pad35)") (class "Default")
      (node (ref "U4") (pin "35") (pinfunction "NC_35") (pintype "unspecified"))
    )
    (net (code "61") (name "unconnected-(U4-NC-Pad36)") (class "Default")
      (node (ref "U4") (pin "36") (pinfunction "NC_36") (pintype "unspecified"))
    )
    (net (code "62") (name "unconnected-(U4-NC-Pad44)") (class "Default")
      (node (ref "U4") (pin "44") (pinfunction "NC_44") (pintype "unspecified"))
    )
    (net (code "63") (name "unconnected-(U4-NC-Pad45)") (class "Default")
      (node (ref "U4") (pin "45") (pinfunction "NC_45") (pintype "unspecified"))
    )
    (net (code "64") (name "unconnected-(U4-NC-Pad47)") (class "Default")
      (node (ref "U4") (pin "47") (pinfunction "NC_47") (pintype "unspecified"))
    )
    (net (code "65") (name "unconnected-(U4-NC-Pad48)") (class "Default")
      (node (ref "U4") (pin "48") (pinfunction "NC_48") (pintype "unspecified"))
    )
    (net (code "66") (name "unconnected-(U4-SD0{slash}IO7-Pad32)") (class "Default")
      (node (ref "U4") (pin "32") (pinfunction "SD0/IO7_32") (pintype "unspecified"))
    )
    (net (code "67") (name "unconnected-(U4-SD1{slash}IO8-Pad33)") (class "Default")
      (node (ref "U4") (pin "33") (pinfunction "SD1/IO8_33") (pintype "unspecified"))
    )
    (net (code "68") (name "unconnected-(U4-SD2{slash}IO9-Pad28)") (class "Default")
      (node (ref "U4") (pin "28") (pinfunction "SD2/IO9_28") (pintype "unspecified"))
    )
    (net (code "69") (name "unconnected-(U4-SD3{slash}IO10-Pad29)") (class "Default")
      (node (ref "U4") (pin "29") (pinfunction "SD3/IO10_29") (pintype "unspecified"))
    )
    (net (code "70") (name "unconnected-(U4-SENSOR_CAPN{slash}I38-Pad7)") (class "Default")
      (node (ref "U4") (pin "7") (pinfunction "SENSOR_CAPN/I38_7") (pintype "unspecified"))
    )
    (net (code "71") (name "unconnected-(U4-SENSOR_CAPP{slash}I37-Pad6)") (class "Default")
      (node (ref "U4") (pin "6") (pinfunction "SENSOR_CAPP/I37_6") (pintype "unspecified"))
    )
    (net (code "72") (name "unconnected-(U4-SENSOR_VN{slash}I39-Pad8)") (class "Default")
      (node (ref "U4") (pin "8") (pinfunction "SENSOR_VN/I39_8") (pintype "unspecified"))
    )
    (net (code "73") (name "unconnected-(U4-SENSOR_VP{slash}I36-Pad5)") (class "Default")
      (node (ref "U4") (pin "5") (pinfunction "SENSOR_VP/I36_5") (pintype "unspecified"))
    )
    (net (code "74") (name "unconnected-(U4-VDET_1{slash}I34-Pad10)") (class "Default")
      (node (ref "U4") (pin "10") (pinfunction "VDET_1/I34_10") (pintype "unspecified"))
    )
    (net (code "75") (name "unconnected-(U4-VDET_2{slash}I35-Pad11)") (class "Default")
      (node (ref "U4") (pin "11") (pinfunction "VDET_2/I35_11") (pintype "unspecified"))
    )
    (net (code "76") (name "unconnected-(U5-GDO2-Pad3)") (class "Default")
      (node (ref "U5") (pin "3") (pinfunction "GDO2_3") (pintype "unspecified"))
    )
  )
)
